# Main485.net
KiCad netlist of a schematic drawn in Altium Designer
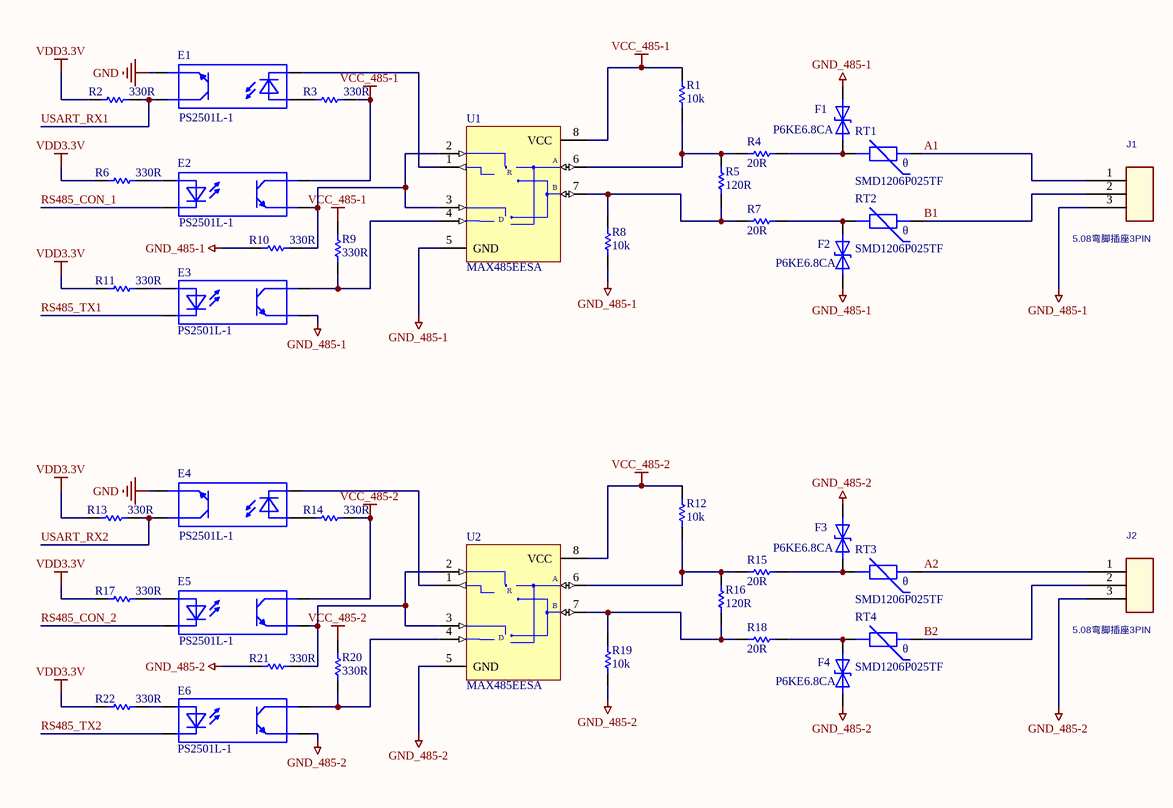
[diagram p0: Main485.SchDoc]

(export (version "E")
  (design (tool "Eeschema 10.0.6"))
  (components
    (comp (ref "E1")
      (value "PS2501L-1")
      (footprint "NEC2501")
      (description "光耦")
      (libsource (lib "*") (part "OPTO1"))
    )
    (comp (ref "E2")
      (value "PS2501L-1")
      (footprint "NEC2501")
      (description "光耦")
      (libsource (lib "*") (part "OPTO1"))
    )
    (comp (ref "E3")
      (value "PS2501L-1")
      (footprint "NEC2501")
      (description "光耦")
      (libsource (lib "*") (part "OPTO1"))
    )
    (comp (ref "E4")
      (value "PS2501L-1")
      (footprint "NEC2501")
      (description "光耦")
      (libsource (lib "*") (part "OPTO1"))
    )
    (comp (ref "E5")
      (value "PS2501L-1")
      (footprint "NEC2501")
      (description "光耦")
      (libsource (lib "*") (part "OPTO1"))
    )
    (comp (ref "E6")
      (value "PS2501L-1")
      (footprint "NEC2501")
      (description "光耦")
      (libsource (lib "*") (part "OPTO1"))
    )
    (comp (ref "F1")
      (value "P6KE6.8CA")
      (footprint "P6KE6,8CA")
      (description "快速瞬变二极管")
      (libsource (lib "*") (part "TVS"))
    )
    (comp (ref "F2")
      (value "P6KE6.8CA")
      (footprint "P6KE6,8CA")
      (description "快速瞬变二极管")
      (libsource (lib "*") (part "TVS"))
    )
    (comp (ref "F3")
      (value "P6KE6.8CA")
      (footprint "P6KE6,8CA")
      (description "快速瞬变二极管")
      (libsource (lib "*") (part "TVS"))
    )
    (comp (ref "F4")
      (value "P6KE6.8CA")
      (footprint "P6KE6,8CA")
      (description "快速瞬变二极管")
      (libsource (lib "*") (part "TVS"))
    )
    (comp (ref "J1") (value "5.08弯脚插座3PIN") (footprint "JIEKE_3PX508") (libsource (lib "*") (part "CON3")))
    (comp (ref "J2") (value "5.08弯脚插座3PIN") (footprint "JIEKE_3PX508") (libsource (lib "*") (part "CON3")))
    (comp (ref "R1")
      (value "10k")
      (footprint "0805")
      (description "Semiconductor Resistor")
      (fields (field (name "Comment") "Res Semi") (field (name "PUBLISHER") "Altium Limited"))
      (libsource (lib "Miscellaneous Devices") (part "Res Semi"))
    )
    (comp (ref "R2")
      (value "330R")
      (footprint "0805")
      (description "Semiconductor Resistor")
      (fields (field (name "Comment") "Res Semi") (field (name "PUBLISHER") "Altium Limited"))
      (libsource (lib "Miscellaneous Devices") (part "Res Semi"))
    )
    (comp (ref "R3")
      (value "330R")
      (footprint "0805")
      (description "Semiconductor Resistor")
      (fields (field (name "Comment") "Res Semi") (field (name "PUBLISHER") "Altium Limited"))
      (libsource (lib "Miscellaneous Devices") (part "Res Semi"))
    )
    (comp (ref "R4")
      (value "20R")
      (footprint "0805")
      (description "Semiconductor Resistor")
      (fields (field (name "Comment") "Res Semi") (field (name "PUBLISHER") "Altium Limited"))
      (libsource (lib "Miscellaneous Devices") (part "Res Semi"))
    )
    (comp (ref "R5")
      (value "120R")
      (footprint "0805")
      (description "Semiconductor Resistor")
      (fields (field (name "Comment") "Res Semi") (field (name "PUBLISHER") "Altium Limited"))
      (libsource (lib "Miscellaneous Devices") (part "Res Semi"))
    )
    (comp (ref "R6")
      (value "330R")
      (footprint "0805")
      (description "Semiconductor Resistor")
      (fields (field (name "Comment") "Res Semi") (field (name "PUBLISHER") "Altium Limited"))
      (libsource (lib "Miscellaneous Devices") (part "Res Semi"))
    )
    (comp (ref "R7")
      (value "20R")
      (footprint "0805")
      (description "Semiconductor Resistor")
      (fields (field (name "Comment") "Res Semi") (field (name "PUBLISHER") "Altium Limited"))
      (libsource (lib "Miscellaneous Devices") (part "Res Semi"))
    )
    (comp (ref "R8")
      (value "10k")
      (footprint "0805")
      (description "Semiconductor Resistor")
      (fields (field (name "Comment") "Res Semi") (field (name "PUBLISHER") "Altium Limited"))
      (libsource (lib "Miscellaneous Devices") (part "Res Semi"))
    )
    (comp (ref "R9")
      (value "330R")
      (footprint "0805")
      (description "Semiconductor Resistor")
      (fields (field (name "Comment") "Res Semi") (field (name "PUBLISHER") "Altium Limited"))
      (libsource (lib "Miscellaneous Devices") (part "Res Semi"))
    )
    (comp (ref "R10")
      (value "330R")
      (footprint "0805")
      (description "Semiconductor Resistor")
      (fields (field (name "Comment") "Res Semi") (field (name "PUBLISHER") "Altium Limited"))
      (libsource (lib "Miscellaneous Devices") (part "Res Semi"))
    )
    (comp (ref "R11")
      (value "330R")
      (footprint "0805")
      (description "Semiconductor Resistor")
      (fields (field (name "Comment") "Res Semi") (field (name "PUBLISHER") "Altium Limited"))
      (libsource (lib "Miscellaneous Devices") (part "Res Semi"))
    )
    (comp (ref "R12")
      (value "10k")
      (footprint "0805")
      (description "Semiconductor Resistor")
      (fields (field (name "Comment") "Res Semi") (field (name "PUBLISHER") "Altium Limited"))
      (libsource (lib "Miscellaneous Devices") (part "Res Semi"))
    )
    (comp (ref "R13")
      (value "330R")
      (footprint "0805")
      (description "Semiconductor Resistor")
      (fields (field (name "Comment") "Res Semi") (field (name "PUBLISHER") "Altium Limited"))
      (libsource (lib "Miscellaneous Devices") (part "Res Semi"))
    )
    (comp (ref "R14")
      (value "330R")
      (footprint "0805")
      (description "Semiconductor Resistor")
      (fields (field (name "Comment") "Res Semi") (field (name "PUBLISHER") "Altium Limited"))
      (libsource (lib "Miscellaneous Devices") (part "Res Semi"))
    )
    (comp (ref "R15")
      (value "20R")
      (footprint "0805")
      (description "Semiconductor Resistor")
      (fields (field (name "Comment") "Res Semi") (field (name "PUBLISHER") "Altium Limited"))
      (libsource (lib "Miscellaneous Devices") (part "Res Semi"))
    )
    (comp (ref "R16")
      (value "120R")
      (footprint "0805")
      (description "Semiconductor Resistor")
      (fields (field (name "Comment") "Res Semi") (field (name "PUBLISHER") "Altium Limited"))
      (libsource (lib "Miscellaneous Devices") (part "Res Semi"))
    )
    (comp (ref "R17")
      (value "330R")
      (footprint "0805")
      (description "Semiconductor Resistor")
      (fields (field (name "Comment") "Res Semi") (field (name "PUBLISHER") "Altium Limited"))
      (libsource (lib "Miscellaneous Devices") (part "Res Semi"))
    )
    (comp (ref "R18")
      (value "20R")
      (footprint "0805")
      (description "Semiconductor Resistor")
      (fields (field (name "Comment") "Res Semi") (field (name "PUBLISHER") "Altium Limited"))
      (libsource (lib "Miscellaneous Devices") (part "Res Semi"))
    )
    (comp (ref "R19")
      (value "10k")
      (footprint "0805")
      (description "Semiconductor Resistor")
      (fields (field (name "Comment") "Res Semi") (field (name "PUBLISHER") "Altium Limited"))
      (libsource (lib "Miscellaneous Devices") (part "Res Semi"))
    )
    (comp (ref "R20")
      (value "330R")
      (footprint "0805")
      (description "Semiconductor Resistor")
      (fields (field (name "Comment") "Res Semi") (field (name "PUBLISHER") "Altium Limited"))
      (libsource (lib "Miscellaneous Devices") (part "Res Semi"))
    )
    (comp (ref "R21")
      (value "330R")
      (footprint "0805")
      (description "Semiconductor Resistor")
      (fields (field (name "Comment") "Res Semi") (field (name "PUBLISHER") "Altium Limited"))
      (libsource (lib "Miscellaneous Devices") (part "Res Semi"))
    )
    (comp (ref "R22")
      (value "330R")
      (footprint "0805")
      (description "Semiconductor Resistor")
      (fields (field (name "Comment") "Res Semi") (field (name "PUBLISHER") "Altium Limited"))
      (libsource (lib "Miscellaneous Devices") (part "Res Semi"))
    )
    (comp (ref "RT1")
      (value "SMD1206P025TF")
      (footprint "1206")
      (description "热敏电阻")
      (libsource (lib "*") (part "PTC"))
    )
    (comp (ref "RT2")
      (value "SMD1206P025TF")
      (footprint "1206")
      (description "热敏电阻")
      (libsource (lib "*") (part "PTC"))
    )
    (comp (ref "RT3")
      (value "SMD1206P025TF")
      (footprint "1206")
      (description "热敏电阻")
      (libsource (lib "*") (part "PTC"))
    )
    (comp (ref "RT4")
      (value "SMD1206P025TF")
      (footprint "1206")
      (description "热敏电阻")
      (libsource (lib "*") (part "PTC"))
    )
    (comp (ref "U1")
      (value "MAX485EESA")
      (footprint "NSO8")
      (description "Low-Power, Slew-Rate-Limited RS-485/RS-422 Transceiver")
      (fields (field (name "PUBLISHER") "Altium Limited"))
      (libsource (lib "main board") (part "MAX485ESA"))
    )
    (comp (ref "U2")
      (value "MAX485EESA")
      (footprint "NSO8")
      (description "Low-Power, Slew-Rate-Limited RS-485/RS-422 Transceiver")
      (fields (field (name "PUBLISHER") "Altium Limited"))
      (libsource (lib "main board") (part "MAX485ESA"))
    )
  )
  (nets
    (net (code "1") (name "/A1") (class "Default")
      (node (ref "J1") (pin "1") (pinfunction "1_1") (pintype "passive"))
      (node (ref "RT1") (pin "2") (pintype "passive"))
    )
    (net (code "2") (name "/A2") (class "Default")
      (node (ref "J2") (pin "1") (pinfunction "1_1") (pintype "passive"))
      (node (ref "RT3") (pin "2") (pintype "passive"))
    )
    (net (code "3") (name "/B1") (class "Default")
      (node (ref "J1") (pin "2") (pinfunction "2_2") (pintype "passive"))
      (node (ref "RT2") (pin "2") (pintype "passive"))
    )
    (net (code "4") (name "/B2") (class "Default")
      (node (ref "J2") (pin "2") (pinfunction "2_2") (pintype "passive"))
      (node (ref "RT4") (pin "2") (pintype "passive"))
    )
    (net (code "5") (name "/RS485_CON_1") (class "Default") (node (ref "E2") (pin "2") (pintype "passive")))
    (net (code "6") (name "/RS485_CON_2") (class "Default") (node (ref "E5") (pin "2") (pintype "passive")))
    (net (code "7") (name "/RS485_TX1") (class "Default") (node (ref "E3") (pin "2") (pintype "passive")))
    (net (code "8") (name "/RS485_TX2") (class "Default") (node (ref "E6") (pin "2") (pintype "passive")))
    (net (code "9") (name "/USART_RX1") (class "Default")
      (node (ref "E1") (pin "4") (pintype "passive"))
      (node (ref "R2") (pin "1") (pinfunction "1_1") (pintype "passive"))
    )
    (net (code "10") (name "/USART_RX2") (class "Default")
      (node (ref "E4") (pin "4") (pintype "passive"))
      (node (ref "R13") (pin "1") (pinfunction "1_1") (pintype "passive"))
    )
    (net (code "11") (name "GND") (class "Default")
      (node (ref "E1") (pin "3") (pintype "passive"))
      (node (ref "E4") (pin "3") (pintype "passive"))
    )
    (net (code "12") (name "GND_485-1") (class "Default")
      (node (ref "E3") (pin "3") (pintype "passive"))
      (node (ref "F1") (pin "1") (pintype "passive"))
      (node (ref "F2") (pin "2") (pintype "passive"))
      (node (ref "J1") (pin "3") (pinfunction "3_3") (pintype "passive"))
      (node (ref "R10") (pin "2") (pinfunction "2_2") (pintype "passive"))
      (node (ref "R8") (pin "2") (pinfunction "2_2") (pintype "passive"))
      (node (ref "U1") (pin "5") (pinfunction "GND_5") (pintype "power_in"))
    )
    (net (code "13") (name "GND_485-2") (class "Default")
      (node (ref "E6") (pin "3") (pintype "passive"))
      (node (ref "F3") (pin "1") (pintype "passive"))
      (node (ref "F4") (pin "2") (pintype "passive"))
      (node (ref "J2") (pin "3") (pinfunction "3_3") (pintype "passive"))
      (node (ref "R19") (pin "2") (pinfunction "2_2") (pintype "passive"))
      (node (ref "R21") (pin "2") (pinfunction "2_2") (pintype "passive"))
      (node (ref "U2") (pin "5") (pinfunction "GND_5") (pintype "power_in"))
    )
    (net (code "14") (name "Net-(E1-Pad1)") (class "Default")
      (node (ref "E1") (pin "1") (pintype "passive"))
      (node (ref "R3") (pin "2") (pinfunction "2_2") (pintype "passive"))
    )
    (net (code "15") (name "Net-(E2-Pad1)") (class "Default")
      (node (ref "E2") (pin "1") (pintype "passive"))
      (node (ref "R6") (pin "1") (pinfunction "1_1") (pintype "passive"))
    )
    (net (code "16") (name "Net-(E3-Pad1)") (class "Default")
      (node (ref "E3") (pin "1") (pintype "passive"))
      (node (ref "R11") (pin "1") (pinfunction "1_1") (pintype "passive"))
    )
    (net (code "17") (name "Net-(E4-Pad1)") (class "Default")
      (node (ref "E4") (pin "1") (pintype "passive"))
      (node (ref "R14") (pin "2") (pinfunction "2_2") (pintype "passive"))
    )
    (net (code "18") (name "Net-(E5-Pad1)") (class "Default")
      (node (ref "E5") (pin "1") (pintype "passive"))
      (node (ref "R17") (pin "1") (pinfunction "1_1") (pintype "passive"))
    )
    (net (code "19") (name "Net-(E6-Pad1)") (class "Default")
      (node (ref "E6") (pin "1") (pintype "passive"))
      (node (ref "R22") (pin "1") (pinfunction "1_1") (pintype "passive"))
    )
    (net (code "20") (name "Net-(F1-Pad2)") (class "Default")
      (node (ref "F1") (pin "2") (pintype "passive"))
      (node (ref "R4") (pin "2") (pinfunction "2_2") (pintype "passive"))
      (node (ref "RT1") (pin "1") (pintype "passive"))
    )
    (net (code "21") (name "Net-(F2-Pad1)") (class "Default")
      (node (ref "F2") (pin "1") (pintype "passive"))
      (node (ref "R7") (pin "2") (pinfunction "2_2") (pintype "passive"))
      (node (ref "RT2") (pin "1") (pintype "passive"))
    )
    (net (code "22") (name "Net-(F3-Pad2)") (class "Default")
      (node (ref "F3") (pin "2") (pintype "passive"))
      (node (ref "R15") (pin "2") (pinfunction "2_2") (pintype "passive"))
      (node (ref "RT3") (pin "1") (pintype "passive"))
    )
    (net (code "23") (name "Net-(F4-Pad1)") (class "Default")
      (node (ref "F4") (pin "1") (pintype "passive"))
      (node (ref "R18") (pin "2") (pinfunction "2_2") (pintype "passive"))
      (node (ref "RT4") (pin "1") (pintype "passive"))
    )
    (net (code "24") (name "Net-(U1-A)") (class "Default")
      (node (ref "R1") (pin "2") (pinfunction "2_2") (pintype "passive"))
      (node (ref "R4") (pin "1") (pinfunction "1_1") (pintype "passive"))
      (node (ref "R5") (pin "1") (pinfunction "1_1") (pintype "passive"))
      (node (ref "U1") (pin "6") (pinfunction "A_6") (pintype "bidirectional"))
    )
    (net (code "25") (name "Net-(U1-B)") (class "Default")
      (node (ref "R5") (pin "2") (pinfunction "2_2") (pintype "passive"))
      (node (ref "R7") (pin "1") (pinfunction "1_1") (pintype "passive"))
      (node (ref "R8") (pin "1") (pinfunction "1_1") (pintype "passive"))
      (node (ref "U1") (pin "7") (pinfunction "B_7") (pintype "bidirectional"))
    )
    (net (code "26") (name "Net-(U1-DE)") (class "Default")
      (node (ref "E2") (pin "3") (pintype "passive"))
      (node (ref "R10") (pin "1") (pinfunction "1_1") (pintype "passive"))
      (node (ref "U1") (pin "2") (pinfunction "~{RE}_2") (pintype "input"))
      (node (ref "U1") (pin "3") (pinfunction "DE_3") (pintype "input"))
    )
    (net (code "27") (name "Net-(U1-DI)") (class "Default")
      (node (ref "E3") (pin "4") (pintype "passive"))
      (node (ref "R9") (pin "2") (pinfunction "2_2") (pintype "passive"))
      (node (ref "U1") (pin "4") (pinfunction "DI_4") (pintype "input"))
    )
    (net (code "28") (name "Net-(U1-RO)") (class "Default")
      (node (ref "E1") (pin "2") (pintype "passive"))
      (node (ref "U1") (pin "1") (pinfunction "RO_1") (pintype "output"))
    )
    (net (code "29") (name "Net-(U2-A)") (class "Default")
      (node (ref "R12") (pin "2") (pinfunction "2_2") (pintype "passive"))
      (node (ref "R15") (pin "1") (pinfunction "1_1") (pintype "passive"))
      (node (ref "R16") (pin "1") (pinfunction "1_1") (pintype "passive"))
      (node (ref "U2") (pin "6") (pinfunction "A_6") (pintype "bidirectional"))
    )
    (net (code "30") (name "Net-(U2-B)") (class "Default")
      (node (ref "R16") (pin "2") (pinfunction "2_2") (pintype "passive"))
      (node (ref "R18") (pin "1") (pinfunction "1_1") (pintype "passive"))
      (node (ref "R19") (pin "1") (pinfunction "1_1") (pintype "passive"))
      (node (ref "U2") (pin "7") (pinfunction "B_7") (pintype "bidirectional"))
    )
    (net (code "31") (name "Net-(U2-DE)") (class "Default")
      (node (ref "E5") (pin "3") (pintype "passive"))
      (node (ref "R21") (pin "1") (pinfunction "1_1") (pintype "passive"))
      (node (ref "U2") (pin "2") (pinfunction "~{RE}_2") (pintype "input"))
      (node (ref "U2") (pin "3") (pinfunction "DE_3") (pintype "input"))
    )
    (net (code "32") (name "Net-(U2-DI)") (class "Default")
      (node (ref "E6") (pin "4") (pintype "passive"))
      (node (ref "R20") (pin "2") (pinfunction "2_2") (pintype "passive"))
      (node (ref "U2") (pin "4") (pinfunction "DI_4") (pintype "input"))
    )
    (net (code "33") (name "Net-(U2-RO)") (class "Default")
      (node (ref "E4") (pin "2") (pintype "passive"))
      (node (ref "U2") (pin "1") (pinfunction "RO_1") (pintype "output"))
    )
    (net (code "34") (name "VCC_485-1") (class "Default")
      (node (ref "E2") (pin "4") (pintype "passive"))
      (node (ref "R1") (pin "1") (pinfunction "1_1") (pintype "passive"))
      (node (ref "R3") (pin "1") (pinfunction "1_1") (pintype "passive"))
      (node (ref "R9") (pin "1") (pinfunction "1_1") (pintype "passive"))
      (node (ref "U1") (pin "8") (pinfunction "VCC_8") (pintype "power_in"))
    )
    (net (code "35") (name "VCC_485-2") (class "Default")
      (node (ref "E5") (pin "4") (pintype "passive"))
      (node (ref "R12") (pin "1") (pinfunction "1_1") (pintype "passive"))
      (node (ref "R14") (pin "1") (pinfunction "1_1") (pintype "passive"))
      (node (ref "R20") (pin "1") (pinfunction "1_1") (pintype "passive"))
      (node (ref "U2") (pin "8") (pinfunction "VCC_8") (pintype "power_in"))
    )
    (net (code "36") (name "VDD3.3V") (class "Default")
      (node (ref "R11") (pin "2") (pinfunction "2_2") (pintype "passive"))
      (node (ref "R13") (pin "2") (pinfunction "2_2") (pintype "passive"))
      (node (ref "R17") (pin "2") (pinfunction "2_2") (pintype "passive"))
      (node (ref "R2") (pin "2") (pinfunction "2_2") (pintype "passive"))
      (node (ref "R22") (pin "2") (pinfunction "2_2") (pintype "passive"))
      (node (ref "R6") (pin "2") (pinfunction "2_2") (pintype "passive"))
    )
  )
)
